# PCODoubleWing.net
KiCad netlist of a schematic drawn in EAGLE
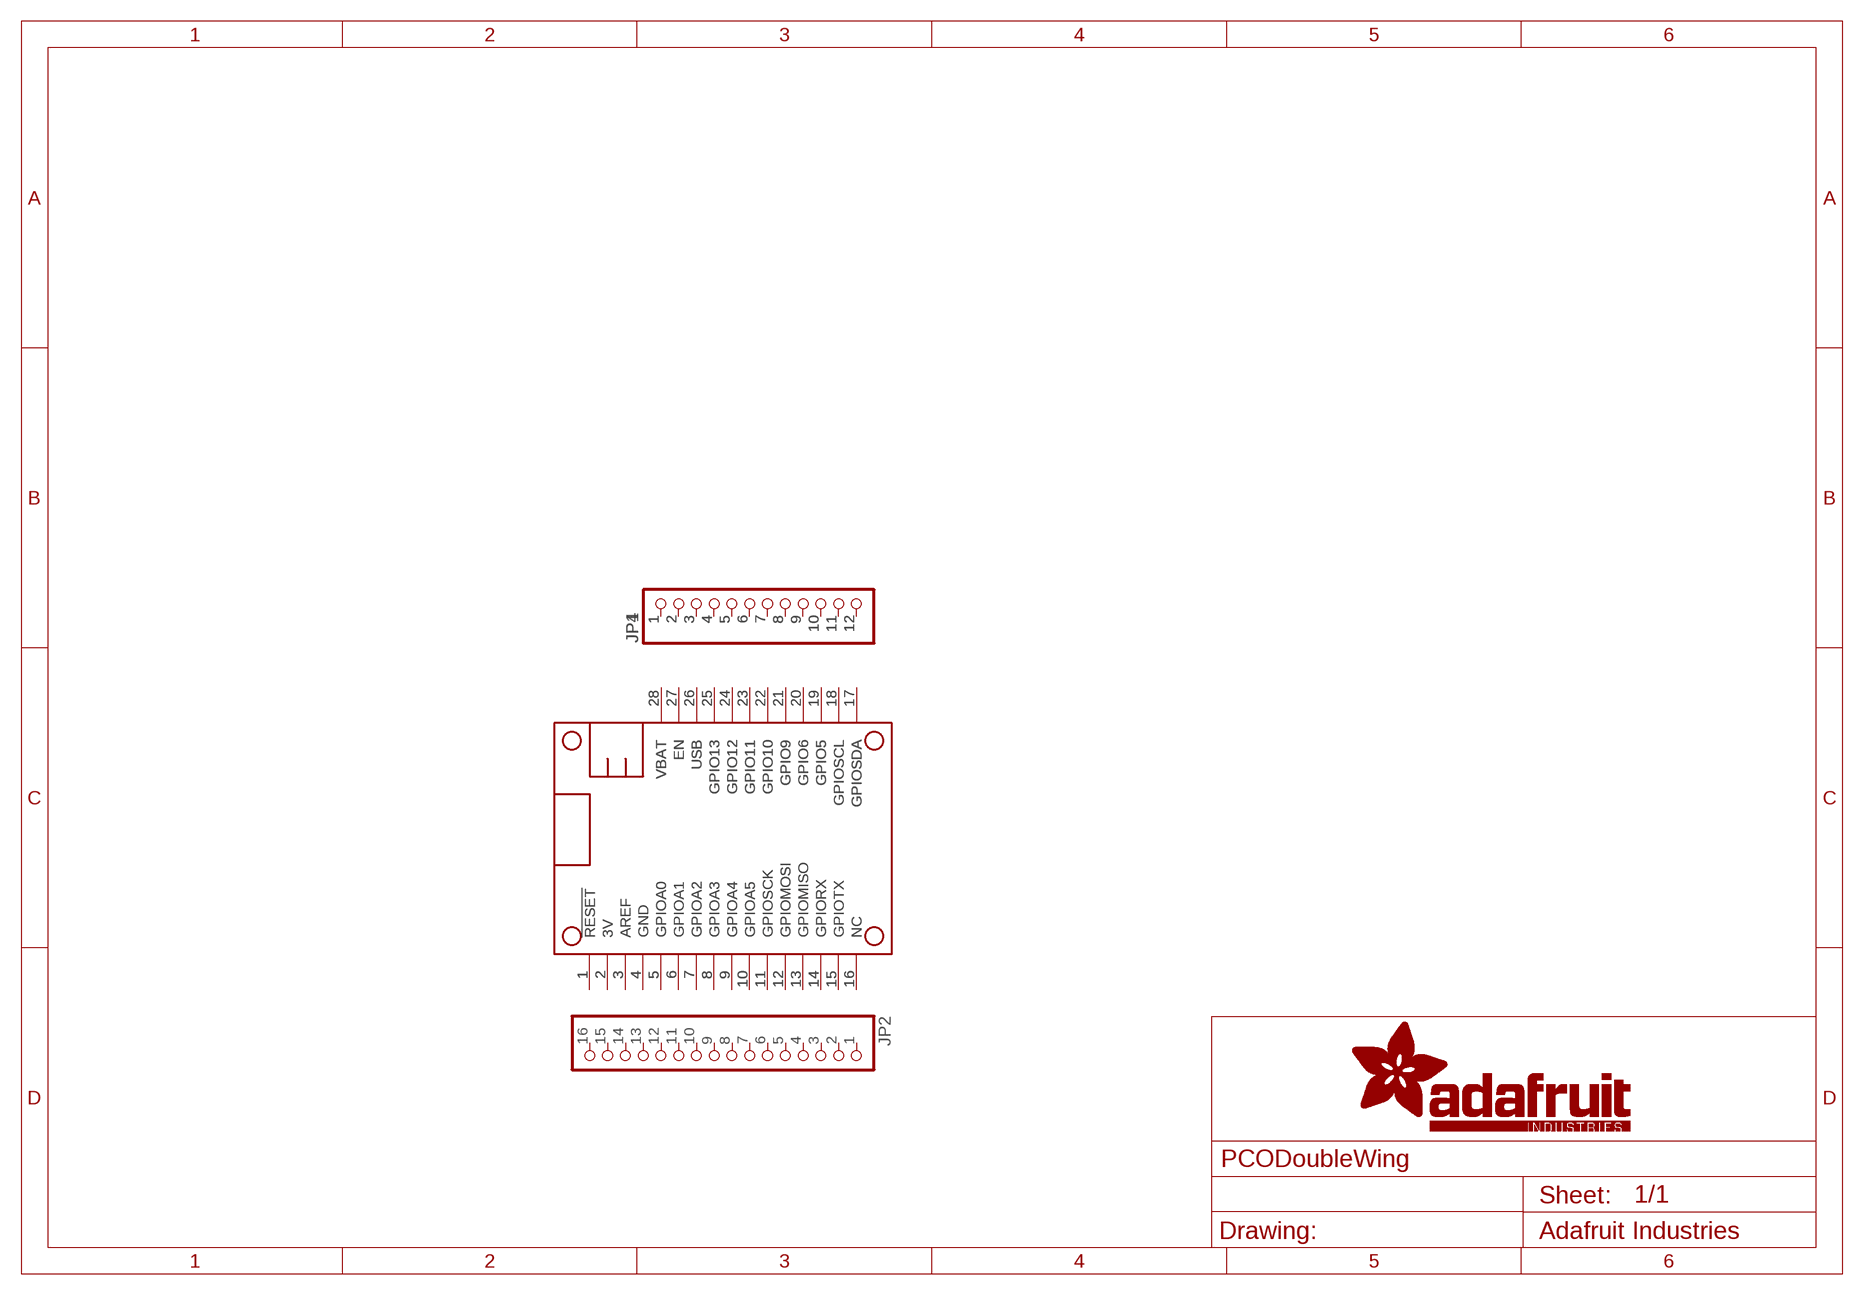
[diagram p0: schematic, sheet 1]

(export (version "E")
  (design (tool "Eeschema 10.0.6"))
  (components
    (comp (ref "JP1")
      (value "HEADER-1X1276MIL")
      (footprint "eagle-import:1X12_ROUND_76MIL")
      (libsource (lib "eagle-import") (part "HEADER-1X1276MIL"))
    )
    (comp (ref "JP2")
      (value "HEADER-1X16_76MIL")
      (footprint "eagle-import:1X16_ROUND_76MIL")
      (libsource (lib "eagle-import") (part "HEADER-1X16_76MIL"))
    )
    (comp (ref "JP4")
      (value "HEADER-1X1276MIL")
      (footprint "eagle-import:1X12_ROUND_76MIL")
      (libsource (lib "eagle-import") (part "HEADER-1X1276MIL"))
    )
    (comp (ref "MS1")
      (value "FEATHERWING_NODIM")
      (footprint "eagle-import:FEATHERWING_DIM")
      (libsource (lib "eagle-import") (part "FEATHERWING_NODIM"))
    )
    (comp (ref "MS2")
      (value "FEATHERWING_NODIM")
      (footprint "eagle-import:FEATHERWING_DIM")
      (libsource (lib "eagle-import") (part "FEATHERWING_NODIM"))
    )
  )
  (nets
    (net (code "1") (name "Net-(JP1-Pad1)") (class "Default")
      (node (ref "JP1") (pin "1") (pinfunction "1_1") (pintype "passive"))
      (node (ref "JP4") (pin "1") (pinfunction "1_1") (pintype "passive"))
    )
    (net (code "2") (name "Net-(JP1-Pad2)") (class "Default")
      (node (ref "JP1") (pin "2") (pinfunction "2_2") (pintype "passive"))
      (node (ref "JP4") (pin "2") (pinfunction "2_2") (pintype "passive"))
    )
    (net (code "3") (name "Net-(JP1-Pad3)") (class "Default")
      (node (ref "JP1") (pin "3") (pinfunction "3_3") (pintype "passive"))
      (node (ref "JP4") (pin "3") (pinfunction "3_3") (pintype "passive"))
    )
    (net (code "4") (name "Net-(JP1-Pad4)") (class "Default")
      (node (ref "JP1") (pin "4") (pinfunction "4_4") (pintype "passive"))
      (node (ref "JP4") (pin "4") (pinfunction "4_4") (pintype "passive"))
    )
    (net (code "5") (name "Net-(JP1-Pad5)") (class "Default")
      (node (ref "JP1") (pin "5") (pinfunction "5_5") (pintype "passive"))
      (node (ref "JP4") (pin "5") (pinfunction "5_5") (pintype "passive"))
    )
    (net (code "6") (name "Net-(JP1-Pad6)") (class "Default")
      (node (ref "JP1") (pin "6") (pinfunction "6_6") (pintype "passive"))
      (node (ref "JP4") (pin "6") (pinfunction "6_6") (pintype "passive"))
    )
    (net (code "7") (name "Net-(JP1-Pad7)") (class "Default")
      (node (ref "JP1") (pin "7") (pinfunction "7_7") (pintype "passive"))
      (node (ref "JP4") (pin "7") (pinfunction "7_7") (pintype "passive"))
    )
    (net (code "8") (name "Net-(JP1-Pad8)") (class "Default")
      (node (ref "JP1") (pin "8") (pinfunction "8_8") (pintype "passive"))
      (node (ref "JP4") (pin "8") (pinfunction "8_8") (pintype "passive"))
    )
    (net (code "9") (name "Net-(JP1-Pad9)") (class "Default")
      (node (ref "JP1") (pin "9") (pinfunction "9_9") (pintype "passive"))
      (node (ref "JP4") (pin "9") (pinfunction "9_9") (pintype "passive"))
    )
    (net (code "10") (name "Net-(JP1-Pad10)") (class "Default")
      (node (ref "JP1") (pin "10") (pinfunction "10_10") (pintype "passive"))
      (node (ref "JP4") (pin "10") (pinfunction "10_10") (pintype "passive"))
    )
    (net (code "11") (name "Net-(JP1-Pad11)") (class "Default")
      (node (ref "JP1") (pin "11") (pinfunction "11_11") (pintype "passive"))
      (node (ref "JP4") (pin "11") (pinfunction "11_11") (pintype "passive"))
    )
    (net (code "12") (name "Net-(JP1-Pad12)") (class "Default")
      (node (ref "JP1") (pin "12") (pinfunction "12_12") (pintype "passive"))
      (node (ref "JP4") (pin "12") (pinfunction "12_12") (pintype "passive"))
    )
    (net (code "13") (name "Net-(MS1-3V)") (class "Default")
      (node (ref "MS1") (pin "2") (pinfunction "3V_2") (pintype "power_in"))
      (node (ref "MS2") (pin "2") (pinfunction "3V_2") (pintype "power_in"))
    )
    (net (code "14") (name "Net-(MS1-AREF)") (class "Default")
      (node (ref "MS1") (pin "3") (pinfunction "AREF_3") (pintype "passive"))
      (node (ref "MS2") (pin "3") (pinfunction "AREF_3") (pintype "passive"))
    )
    (net (code "15") (name "Net-(MS1-EN)") (class "Default")
      (node (ref "MS1") (pin "27") (pinfunction "EN_27") (pintype "passive"))
      (node (ref "MS2") (pin "27") (pinfunction "EN_27") (pintype "passive"))
    )
    (net (code "16") (name "Net-(MS1-GND)") (class "Default")
      (node (ref "MS1") (pin "4") (pinfunction "GND_4") (pintype "power_in"))
      (node (ref "MS2") (pin "4") (pinfunction "GND_4") (pintype "power_in"))
    )
    (net (code "17") (name "Net-(MS1-GPIO5)") (class "Default")
      (node (ref "MS1") (pin "19") (pinfunction "GPIO5_19") (pintype "bidirectional"))
      (node (ref "MS2") (pin "19") (pinfunction "GPIO5_19") (pintype "bidirectional"))
    )
    (net (code "18") (name "Net-(MS1-GPIO6)") (class "Default")
      (node (ref "MS1") (pin "20") (pinfunction "GPIO6_20") (pintype "bidirectional"))
      (node (ref "MS2") (pin "20") (pinfunction "GPIO6_20") (pintype "bidirectional"))
    )
    (net (code "19") (name "Net-(MS1-GPIO9)") (class "Default")
      (node (ref "MS1") (pin "21") (pinfunction "GPIO9_21") (pintype "bidirectional"))
      (node (ref "MS2") (pin "21") (pinfunction "GPIO9_21") (pintype "bidirectional"))
    )
    (net (code "20") (name "Net-(MS1-GPIO10)") (class "Default")
      (node (ref "MS1") (pin "22") (pinfunction "GPIO10_22") (pintype "bidirectional"))
      (node (ref "MS2") (pin "22") (pinfunction "GPIO10_22") (pintype "bidirectional"))
    )
    (net (code "21") (name "Net-(MS1-GPIO11)") (class "Default")
      (node (ref "MS1") (pin "23") (pinfunction "GPIO11_23") (pintype "bidirectional"))
      (node (ref "MS2") (pin "23") (pinfunction "GPIO11_23") (pintype "bidirectional"))
    )
    (net (code "22") (name "Net-(MS1-GPIO12)") (class "Default")
      (node (ref "MS1") (pin "24") (pinfunction "GPIO12_24") (pintype "bidirectional"))
      (node (ref "MS2") (pin "24") (pinfunction "GPIO12_24") (pintype "bidirectional"))
    )
    (net (code "23") (name "Net-(MS1-GPIO13)") (class "Default")
      (node (ref "MS1") (pin "25") (pinfunction "GPIO13_25") (pintype "bidirectional"))
      (node (ref "MS2") (pin "25") (pinfunction "GPIO13_25") (pintype "bidirectional"))
    )
    (net (code "24") (name "Net-(MS1-GPIOA0)") (class "Default")
      (node (ref "MS1") (pin "5") (pinfunction "GPIOA0_5") (pintype "bidirectional"))
      (node (ref "MS2") (pin "5") (pinfunction "GPIOA0_5") (pintype "bidirectional"))
    )
    (net (code "25") (name "Net-(MS1-GPIOA1)") (class "Default")
      (node (ref "MS1") (pin "6") (pinfunction "GPIOA1_6") (pintype "bidirectional"))
      (node (ref "MS2") (pin "6") (pinfunction "GPIOA1_6") (pintype "bidirectional"))
    )
    (net (code "26") (name "Net-(MS1-GPIOA2)") (class "Default")
      (node (ref "MS1") (pin "7") (pinfunction "GPIOA2_7") (pintype "bidirectional"))
      (node (ref "MS2") (pin "7") (pinfunction "GPIOA2_7") (pintype "bidirectional"))
    )
    (net (code "27") (name "Net-(MS1-GPIOA3)") (class "Default")
      (node (ref "MS1") (pin "8") (pinfunction "GPIOA3_8") (pintype "bidirectional"))
      (node (ref "MS2") (pin "8") (pinfunction "GPIOA3_8") (pintype "bidirectional"))
    )
    (net (code "28") (name "Net-(MS1-GPIOA4)") (class "Default")
      (node (ref "MS1") (pin "9") (pinfunction "GPIOA4_9") (pintype "bidirectional"))
      (node (ref "MS2") (pin "9") (pinfunction "GPIOA4_9") (pintype "bidirectional"))
    )
    (net (code "29") (name "Net-(MS1-GPIOA5)") (class "Default")
      (node (ref "MS1") (pin "10") (pinfunction "GPIOA5_10") (pintype "bidirectional"))
      (node (ref "MS2") (pin "10") (pinfunction "GPIOA5_10") (pintype "bidirectional"))
    )
    (net (code "30") (name "Net-(MS1-GPIOMISO)") (class "Default")
      (node (ref "MS1") (pin "13") (pinfunction "GPIOMISO_13") (pintype "bidirectional"))
      (node (ref "MS2") (pin "13") (pinfunction "GPIOMISO_13") (pintype "bidirectional"))
    )
    (net (code "31") (name "Net-(MS1-GPIOMOSI)") (class "Default")
      (node (ref "MS1") (pin "12") (pinfunction "GPIOMOSI_12") (pintype "bidirectional"))
      (node (ref "MS2") (pin "12") (pinfunction "GPIOMOSI_12") (pintype "bidirectional"))
    )
    (net (code "32") (name "Net-(MS1-GPIORX)") (class "Default")
      (node (ref "MS1") (pin "14") (pinfunction "GPIORX_14") (pintype "bidirectional"))
      (node (ref "MS2") (pin "14") (pinfunction "GPIORX_14") (pintype "bidirectional"))
    )
    (net (code "33") (name "Net-(MS1-GPIOSCK)") (class "Default")
      (node (ref "MS1") (pin "11") (pinfunction "GPIOSCK_11") (pintype "bidirectional"))
      (node (ref "MS2") (pin "11") (pinfunction "GPIOSCK_11") (pintype "bidirectional"))
    )
    (net (code "34") (name "Net-(MS1-GPIOSCL)") (class "Default")
      (node (ref "MS1") (pin "18") (pinfunction "GPIOSCL_18") (pintype "bidirectional"))
      (node (ref "MS2") (pin "18") (pinfunction "GPIOSCL_18") (pintype "bidirectional"))
    )
    (net (code "35") (name "Net-(MS1-GPIOSDA)") (class "Default")
      (node (ref "MS1") (pin "17") (pinfunction "GPIOSDA_17") (pintype "bidirectional"))
      (node (ref "MS2") (pin "17") (pinfunction "GPIOSDA_17") (pintype "bidirectional"))
    )
    (net (code "36") (name "Net-(MS1-GPIOTX)") (class "Default")
      (node (ref "MS1") (pin "15") (pinfunction "GPIOTX_15") (pintype "bidirectional"))
      (node (ref "MS2") (pin "15") (pinfunction "GPIOTX_15") (pintype "bidirectional"))
    )
    (net (code "37") (name "Net-(MS1-NC)") (class "Default")
      (node (ref "MS1") (pin "16") (pinfunction "NC_16") (pintype "passive"))
      (node (ref "MS2") (pin "16") (pinfunction "NC_16") (pintype "passive"))
    )
    (net (code "38") (name "Net-(MS1-USB)") (class "Default")
      (node (ref "MS1") (pin "26") (pinfunction "USB_26") (pintype "power_in"))
      (node (ref "MS2") (pin "26") (pinfunction "USB_26") (pintype "power_in"))
    )
    (net (code "39") (name "Net-(MS1-VBAT)") (class "Default")
      (node (ref "MS1") (pin "28") (pinfunction "VBAT_28") (pintype "power_in"))
      (node (ref "MS2") (pin "28") (pinfunction "VBAT_28") (pintype "power_in"))
    )
    (net (code "40") (name "Net-(MS1-~{RESET})") (class "Default")
      (node (ref "MS1") (pin "1") (pinfunction "~{RESET}_1") (pintype "input"))
      (node (ref "MS2") (pin "1") (pinfunction "~{RESET}_1") (pintype "input"))
    )
    (net (code "41") (name "unconnected-(JP2-Pad1)") (class "Default")
      (node (ref "JP2") (pin "1") (pinfunction "1_1") (pintype "passive"))
    )
    (net (code "42") (name "unconnected-(JP2-Pad2)") (class "Default")
      (node (ref "JP2") (pin "2") (pinfunction "2_2") (pintype "passive"))
    )
    (net (code "43") (name "unconnected-(JP2-Pad3)") (class "Default")
      (node (ref "JP2") (pin "3") (pinfunction "3_3") (pintype "passive"))
    )
    (net (code "44") (name "unconnected-(JP2-Pad4)") (class "Default")
      (node (ref "JP2") (pin "4") (pinfunction "4_4") (pintype "passive"))
    )
    (net (code "45") (name "unconnected-(JP2-Pad5)") (class "Default")
      (node (ref "JP2") (pin "5") (pinfunction "5_5") (pintype "passive"))
    )
    (net (code "46") (name "unconnected-(JP2-Pad6)") (class "Default")
      (node (ref "JP2") (pin "6") (pinfunction "6_6") (pintype "passive"))
    )
    (net (code "47") (name "unconnected-(JP2-Pad7)") (class "Default")
      (node (ref "JP2") (pin "7") (pinfunction "7_7") (pintype "passive"))
    )
    (net (code "48") (name "unconnected-(JP2-Pad8)") (class "Default")
      (node (ref "JP2") (pin "8") (pinfunction "8_8") (pintype "passive"))
    )
    (net (code "49") (name "unconnected-(JP2-Pad9)") (class "Default")
      (node (ref "JP2") (pin "9") (pinfunction "9_9") (pintype "passive"))
    )
    (net (code "50") (name "unconnected-(JP2-Pad10)") (class "Default")
      (node (ref "JP2") (pin "10") (pinfunction "10_10") (pintype "passive"))
    )
    (net (code "51") (name "unconnected-(JP2-Pad11)") (class "Default")
      (node (ref "JP2") (pin "11") (pinfunction "11_11") (pintype "passive"))
    )
    (net (code "52") (name "unconnected-(JP2-Pad12)") (class "Default")
      (node (ref "JP2") (pin "12") (pinfunction "12_12") (pintype "passive"))
    )
    (net (code "53") (name "unconnected-(JP2-Pad13)") (class "Default")
      (node (ref "JP2") (pin "13") (pinfunction "13_13") (pintype "passive"))
    )
    (net (code "54") (name "unconnected-(JP2-Pad14)") (class "Default")
      (node (ref "JP2") (pin "14") (pinfunction "14_14") (pintype "passive"))
    )
    (net (code "55") (name "unconnected-(JP2-Pad15)") (class "Default")
      (node (ref "JP2") (pin "15") (pinfunction "15_15") (pintype "passive"))
    )
    (net (code "56") (name "unconnected-(JP2-Pad16)") (class "Default")
      (node (ref "JP2") (pin "16") (pinfunction "16_16") (pintype "passive"))
    )
  )
)
